# mother3.net
KiCad netlist of a schematic drawn in EAGLE
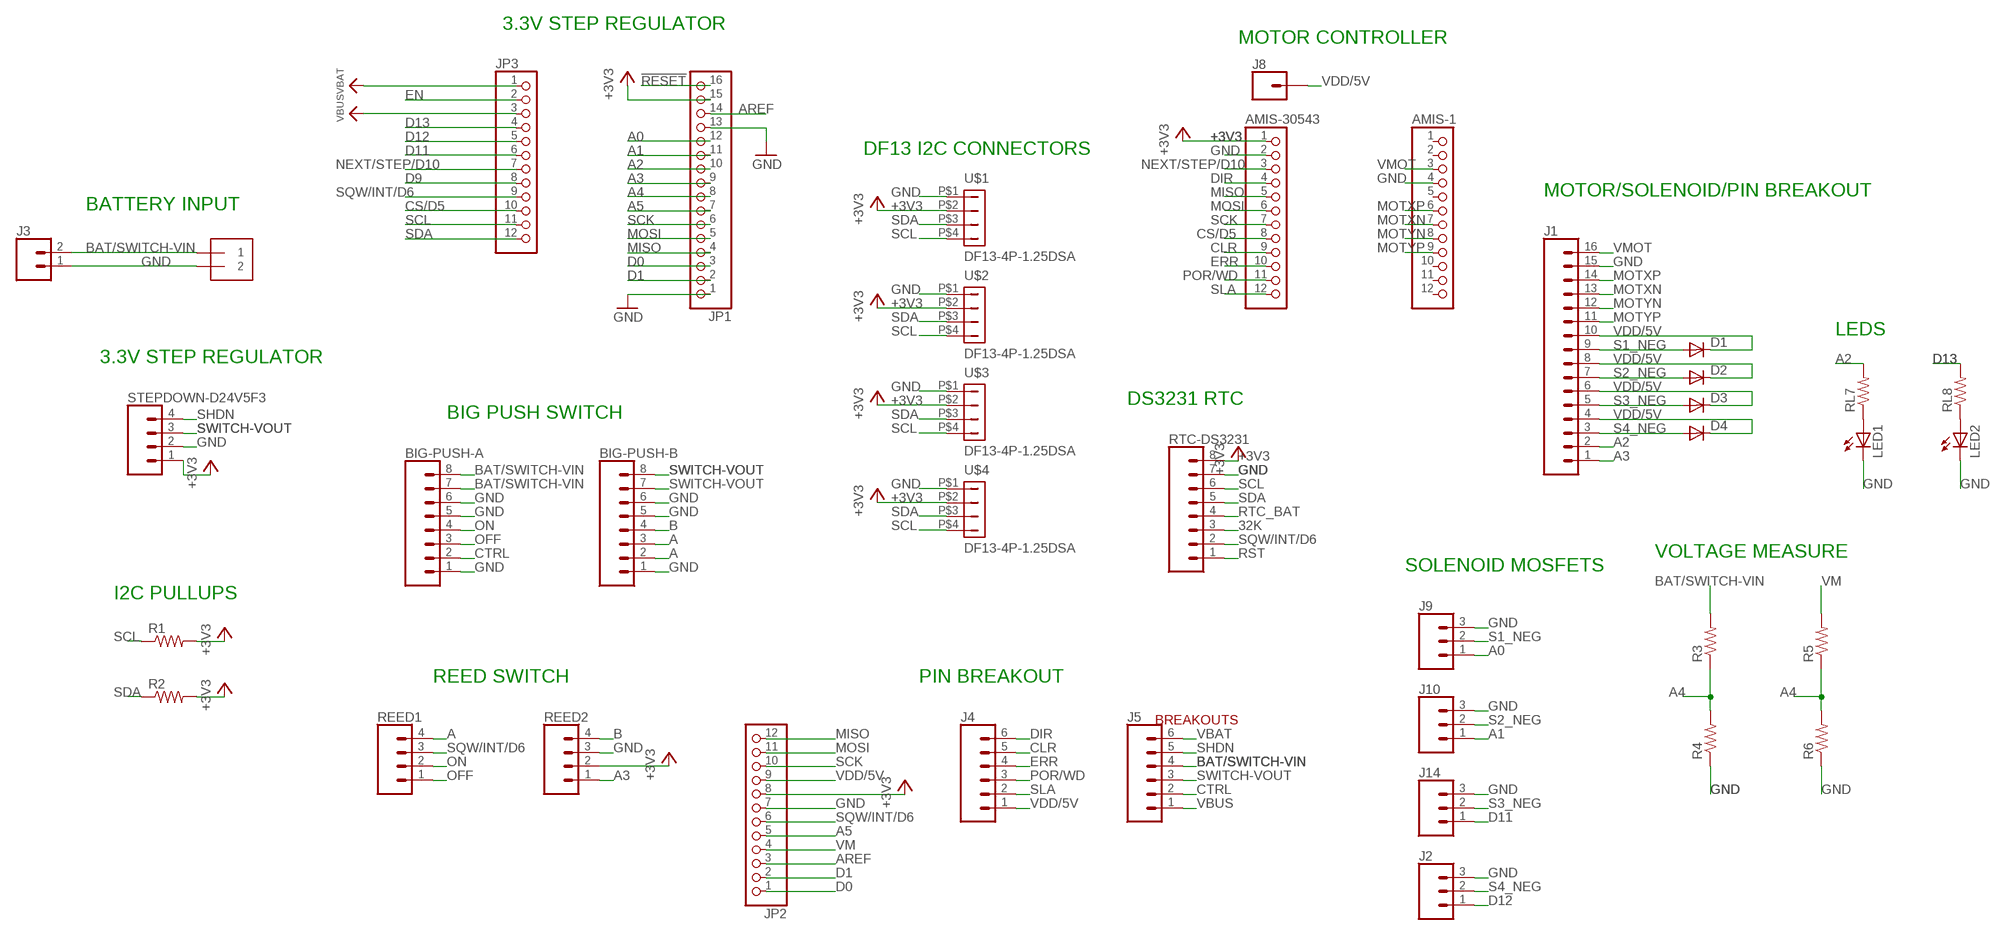
[diagram p0: schematic, sheet 1]

(export (version "E")
  (design (tool "Eeschema 10.0.6"))
  (components
    (comp (ref "AMIS-1")
      (value "PINHD-1X12-CB")
      (footprint "eagle-import:1X12-CB")
      (libsource (lib "eagle-import") (part "PINHD-1X12-CB"))
    )
    (comp (ref "AMIS-30543")
      (value "PINHD-1X12-CB")
      (footprint "eagle-import:1X12-CB")
      (libsource (lib "eagle-import") (part "PINHD-1X12-CB"))
    )
    (comp (ref "BAT")
      (value "1X2-3.5MM")
      (footprint "eagle-import:1X2-3.5MM")
      (libsource (lib "eagle-import") (part "1X2-3.5MM"))
    )
    (comp (ref "BIG-PUSH-A")
      (value "CONN_08\"")
      (footprint "eagle-import:1X08")
      (libsource (lib "eagle-import") (part "CONN_08{dblquote}"))
    )
    (comp (ref "BIG-PUSH-B")
      (value "CONN_08\"")
      (footprint "eagle-import:1X08")
      (libsource (lib "eagle-import") (part "CONN_08{dblquote}"))
    )
    (comp (ref "D1")
      (value "1N4148DO35-7")
      (footprint "eagle-import:DO35-7")
      (libsource (lib "eagle-import") (part "1N4148DO35-7"))
    )
    (comp (ref "D2")
      (value "1N4148DO35-7")
      (footprint "eagle-import:DO35-7")
      (libsource (lib "eagle-import") (part "1N4148DO35-7"))
    )
    (comp (ref "D3")
      (value "1N4148DO35-7")
      (footprint "eagle-import:DO35-7")
      (libsource (lib "eagle-import") (part "1N4148DO35-7"))
    )
    (comp (ref "D4")
      (value "1N4148DO35-7")
      (footprint "eagle-import:DO35-7")
      (libsource (lib "eagle-import") (part "1N4148DO35-7"))
    )
    (comp (ref "J1")
      (value "CONN_16")
      (footprint "eagle-import:1X16")
      (libsource (lib "eagle-import") (part "CONN_16"))
    )
    (comp (ref "J2")
      (value "CONN_03")
      (footprint "eagle-import:1X03")
      (libsource (lib "eagle-import") (part "CONN_03"))
    )
    (comp (ref "J3")
      (value "CONN_02")
      (footprint "eagle-import:1X02")
      (libsource (lib "eagle-import") (part "CONN_02"))
    )
    (comp (ref "J4")
      (value "CONN_06SILK_FEMALE_PTH")
      (footprint "eagle-import:1X06")
      (libsource (lib "eagle-import") (part "CONN_06SILK_FEMALE_PTH"))
    )
    (comp (ref "J5")
      (value "CONN_06SILK_FEMALE_PTH")
      (footprint "eagle-import:1X06")
      (libsource (lib "eagle-import") (part "CONN_06SILK_FEMALE_PTH"))
    )
    (comp (ref "J8")
      (value "CONN_01")
      (footprint "eagle-import:1X01")
      (libsource (lib "eagle-import") (part "CONN_01"))
    )
    (comp (ref "J9")
      (value "CONN_03")
      (footprint "eagle-import:1X03")
      (libsource (lib "eagle-import") (part "CONN_03"))
    )
    (comp (ref "J10")
      (value "CONN_03")
      (footprint "eagle-import:1X03")
      (libsource (lib "eagle-import") (part "CONN_03"))
    )
    (comp (ref "J14")
      (value "CONN_03")
      (footprint "eagle-import:1X03")
      (libsource (lib "eagle-import") (part "CONN_03"))
    )
    (comp (ref "JP1")
      (value "HEADER-1X16ROUND")
      (footprint "eagle-import:1X16_ROUND")
      (libsource (lib "eagle-import") (part "HEADER-1X16ROUND"))
    )
    (comp (ref "JP2")
      (value "HEADER-1X12")
      (footprint "eagle-import:1X12_ROUND")
      (libsource (lib "eagle-import") (part "HEADER-1X12"))
    )
    (comp (ref "JP3")
      (value "HEADER-1X12")
      (footprint "eagle-import:1X12_ROUND")
      (libsource (lib "eagle-import") (part "HEADER-1X12"))
    )
    (comp (ref "LED1")
      (value "LED5MM")
      (footprint "eagle-import:LED5MM")
      (libsource (lib "eagle-import") (part "LED5MM"))
    )
    (comp (ref "LED2")
      (value "LED5MM")
      (footprint "eagle-import:LED5MM")
      (libsource (lib "eagle-import") (part "LED5MM"))
    )
    (comp (ref "R1")
      (value "R-US_0207/10")
      (footprint "eagle-import:0207_10")
      (libsource (lib "eagle-import") (part "R-US_0207/10"))
    )
    (comp (ref "R2")
      (value "R-US_0207/10")
      (footprint "eagle-import:0207_10")
      (libsource (lib "eagle-import") (part "R-US_0207/10"))
    )
    (comp (ref "R3")
      (value "R-US_0207/10")
      (footprint "eagle-import:0207_10")
      (libsource (lib "eagle-import") (part "R-US_0207/10"))
    )
    (comp (ref "R4")
      (value "R-US_0207/10")
      (footprint "eagle-import:0207_10")
      (libsource (lib "eagle-import") (part "R-US_0207/10"))
    )
    (comp (ref "R5")
      (value "R-US_0207/10")
      (footprint "eagle-import:0207_10")
      (libsource (lib "eagle-import") (part "R-US_0207/10"))
    )
    (comp (ref "R6")
      (value "R-US_0207/10")
      (footprint "eagle-import:0207_10")
      (libsource (lib "eagle-import") (part "R-US_0207/10"))
    )
    (comp (ref "REED1")
      (value "CONN_04")
      (footprint "eagle-import:1X04")
      (libsource (lib "eagle-import") (part "CONN_04"))
    )
    (comp (ref "REED2")
      (value "CONN_04")
      (footprint "eagle-import:1X04")
      (libsource (lib "eagle-import") (part "CONN_04"))
    )
    (comp (ref "RL7")
      (value "R-US_0207/10")
      (footprint "eagle-import:0207_10")
      (libsource (lib "eagle-import") (part "R-US_0207/10"))
    )
    (comp (ref "RL8")
      (value "R-US_0207/10")
      (footprint "eagle-import:0207_10")
      (libsource (lib "eagle-import") (part "R-US_0207/10"))
    )
    (comp (ref "RTC-DS3231")
      (value "CONN_08\"")
      (footprint "eagle-import:1X08")
      (libsource (lib "eagle-import") (part "CONN_08{dblquote}"))
    )
    (comp (ref "STEPDOWN-D24V5F3")
      (value "CONN_04")
      (footprint "eagle-import:1X04")
      (libsource (lib "eagle-import") (part "CONN_04"))
    )
    (comp (ref "U$1")
      (value "DF13-4P-1.25DSA")
      (footprint "eagle-import:DF13-4P-1.25DSA")
      (libsource (lib "eagle-import") (part "DF13-4P-1.25DSA"))
    )
    (comp (ref "U$2")
      (value "DF13-4P-1.25DSA")
      (footprint "eagle-import:DF13-4P-1.25DSA")
      (libsource (lib "eagle-import") (part "DF13-4P-1.25DSA"))
    )
    (comp (ref "U$3")
      (value "DF13-4P-1.25DSA")
      (footprint "eagle-import:DF13-4P-1.25DSA")
      (libsource (lib "eagle-import") (part "DF13-4P-1.25DSA"))
    )
    (comp (ref "U$4")
      (value "DF13-4P-1.25DSA")
      (footprint "eagle-import:DF13-4P-1.25DSA")
      (libsource (lib "eagle-import") (part "DF13-4P-1.25DSA"))
    )
  )
  (nets
    (net (code "1") (name "+3V3") (class "Default")
      (node (ref "AMIS-30543") (pin "1") (pinfunction "1_1") (pintype "passive"))
      (node (ref "JP1") (pin "15") (pinfunction "15_15") (pintype "passive"))
      (node (ref "JP2") (pin "8") (pinfunction "8_8") (pintype "passive"))
      (node (ref "R1") (pin "2") (pinfunction "2_2") (pintype "passive"))
      (node (ref "R2") (pin "2") (pinfunction "2_2") (pintype "passive"))
      (node (ref "REED2") (pin "2") (pinfunction "2_2") (pintype "passive"))
      (node (ref "RTC-DS3231") (pin "8") (pinfunction "8_8") (pintype "passive"))
      (node (ref "STEPDOWN-D24V5F3") (pin "1") (pinfunction "1_1") (pintype "passive"))
      (node (ref "U$1") (pin "P$2") (pinfunction "2_P$2") (pintype "passive"))
      (node (ref "U$2") (pin "P$2") (pinfunction "2_P$2") (pintype "passive"))
      (node (ref "U$3") (pin "P$2") (pinfunction "2_P$2") (pintype "passive"))
      (node (ref "U$4") (pin "P$2") (pinfunction "2_P$2") (pintype "passive"))
    )
    (net (code "2") (name "/32K") (class "Default")
      (node (ref "RTC-DS3231") (pin "3") (pinfunction "3_3") (pintype "passive"))
    )
    (net (code "3") (name "/A") (class "Default")
      (node (ref "BIG-PUSH-B") (pin "2") (pinfunction "2_2") (pintype "passive"))
      (node (ref "BIG-PUSH-B") (pin "3") (pinfunction "3_3") (pintype "passive"))
      (node (ref "REED1") (pin "4") (pinfunction "4_4") (pintype "passive"))
    )
    (net (code "4") (name "/A0") (class "Default")
      (node (ref "J9") (pin "1") (pinfunction "1_1") (pintype "passive"))
      (node (ref "JP1") (pin "12") (pinfunction "12_12") (pintype "passive"))
    )
    (net (code "5") (name "/A1") (class "Default")
      (node (ref "J10") (pin "1") (pinfunction "1_1") (pintype "passive"))
      (node (ref "JP1") (pin "11") (pinfunction "11_11") (pintype "passive"))
    )
    (net (code "6") (name "/A2") (class "Default")
      (node (ref "J1") (pin "2") (pinfunction "2_2") (pintype "passive"))
      (node (ref "JP1") (pin "10") (pinfunction "10_10") (pintype "passive"))
      (node (ref "RL7") (pin "2") (pinfunction "2_2") (pintype "passive"))
    )
    (net (code "7") (name "/A3") (class "Default")
      (node (ref "J1") (pin "1") (pinfunction "1_1") (pintype "passive"))
      (node (ref "JP1") (pin "9") (pinfunction "9_9") (pintype "passive"))
      (node (ref "REED2") (pin "1") (pinfunction "1_1") (pintype "passive"))
    )
    (net (code "8") (name "/A4") (class "Default")
      (node (ref "JP1") (pin "8") (pinfunction "8_8") (pintype "passive"))
      (node (ref "R3") (pin "1") (pinfunction "1_1") (pintype "passive"))
      (node (ref "R4") (pin "2") (pinfunction "2_2") (pintype "passive"))
      (node (ref "R5") (pin "1") (pinfunction "1_1") (pintype "passive"))
      (node (ref "R6") (pin "2") (pinfunction "2_2") (pintype "passive"))
    )
    (net (code "9") (name "/A5") (class "Default")
      (node (ref "JP1") (pin "7") (pinfunction "7_7") (pintype "passive"))
      (node (ref "JP2") (pin "5") (pinfunction "5_5") (pintype "passive"))
    )
    (net (code "10") (name "/AREF") (class "Default")
      (node (ref "JP1") (pin "14") (pinfunction "14_14") (pintype "passive"))
      (node (ref "JP2") (pin "3") (pinfunction "3_3") (pintype "passive"))
    )
    (net (code "11") (name "/B") (class "Default")
      (node (ref "BIG-PUSH-B") (pin "4") (pinfunction "4_4") (pintype "passive"))
      (node (ref "REED2") (pin "4") (pinfunction "4_4") (pintype "passive"))
    )
    (net (code "12") (name "/BAT{slash}SWITCH-VIN") (class "Default")
      (node (ref "BAT") (pin "1") (pinfunction "1_1") (pintype "passive"))
      (node (ref "BIG-PUSH-A") (pin "7") (pinfunction "7_7") (pintype "passive"))
      (node (ref "BIG-PUSH-A") (pin "8") (pinfunction "8_8") (pintype "passive"))
      (node (ref "J3") (pin "2") (pinfunction "2_2") (pintype "passive"))
      (node (ref "J5") (pin "4") (pinfunction "4_4") (pintype "passive"))
      (node (ref "R3") (pin "2") (pinfunction "2_2") (pintype "passive"))
    )
    (net (code "13") (name "/CLR") (class "Default")
      (node (ref "AMIS-30543") (pin "9") (pinfunction "9_9") (pintype "passive"))
      (node (ref "J4") (pin "5") (pinfunction "5_5") (pintype "passive"))
    )
    (net (code "14") (name "/CS{slash}D5") (class "Default")
      (node (ref "AMIS-30543") (pin "8") (pinfunction "8_8") (pintype "passive"))
      (node (ref "JP3") (pin "10") (pinfunction "10_10") (pintype "passive"))
    )
    (net (code "15") (name "/CTRL") (class "Default")
      (node (ref "BIG-PUSH-A") (pin "2") (pinfunction "2_2") (pintype "passive"))
      (node (ref "J5") (pin "2") (pinfunction "2_2") (pintype "passive"))
    )
    (net (code "16") (name "/D0") (class "Default")
      (node (ref "JP1") (pin "3") (pinfunction "3_3") (pintype "passive"))
      (node (ref "JP2") (pin "1") (pinfunction "1_1") (pintype "passive"))
    )
    (net (code "17") (name "/D1") (class "Default")
      (node (ref "JP1") (pin "2") (pinfunction "2_2") (pintype "passive"))
      (node (ref "JP2") (pin "2") (pinfunction "2_2") (pintype "passive"))
    )
    (net (code "18") (name "/D9") (class "Default")
      (node (ref "JP3") (pin "8") (pinfunction "8_8") (pintype "passive"))
    )
    (net (code "19") (name "/D11") (class "Default")
      (node (ref "J14") (pin "1") (pinfunction "1_1") (pintype "passive"))
      (node (ref "JP3") (pin "6") (pinfunction "6_6") (pintype "passive"))
    )
    (net (code "20") (name "/D12") (class "Default")
      (node (ref "J2") (pin "1") (pinfunction "1_1") (pintype "passive"))
      (node (ref "JP3") (pin "5") (pinfunction "5_5") (pintype "passive"))
    )
    (net (code "21") (name "/D13") (class "Default")
      (node (ref "JP3") (pin "4") (pinfunction "4_4") (pintype "passive"))
      (node (ref "RL8") (pin "2") (pinfunction "2_2") (pintype "passive"))
    )
    (net (code "22") (name "/DIR") (class "Default")
      (node (ref "AMIS-30543") (pin "4") (pinfunction "4_4") (pintype "passive"))
      (node (ref "J4") (pin "6") (pinfunction "6_6") (pintype "passive"))
    )
    (net (code "23") (name "/EN") (class "Default")
      (node (ref "JP3") (pin "2") (pinfunction "2_2") (pintype "passive"))
    )
    (net (code "24") (name "/ERR") (class "Default")
      (node (ref "AMIS-30543") (pin "10") (pinfunction "10_10") (pintype "passive"))
      (node (ref "J4") (pin "4") (pinfunction "4_4") (pintype "passive"))
    )
    (net (code "25") (name "/MISO") (class "Default")
      (node (ref "AMIS-30543") (pin "5") (pinfunction "5_5") (pintype "passive"))
      (node (ref "JP1") (pin "4") (pinfunction "4_4") (pintype "passive"))
      (node (ref "JP2") (pin "12") (pinfunction "12_12") (pintype "passive"))
    )
    (net (code "26") (name "/MOSI") (class "Default")
      (node (ref "AMIS-30543") (pin "6") (pinfunction "6_6") (pintype "passive"))
      (node (ref "JP1") (pin "5") (pinfunction "5_5") (pintype "passive"))
      (node (ref "JP2") (pin "11") (pinfunction "11_11") (pintype "passive"))
    )
    (net (code "27") (name "/MOTXN") (class "Default")
      (node (ref "AMIS-1") (pin "7") (pinfunction "7_7") (pintype "passive"))
      (node (ref "J1") (pin "13") (pinfunction "13_13") (pintype "passive"))
    )
    (net (code "28") (name "/MOTXP") (class "Default")
      (node (ref "AMIS-1") (pin "6") (pinfunction "6_6") (pintype "passive"))
      (node (ref "J1") (pin "14") (pinfunction "14_14") (pintype "passive"))
    )
    (net (code "29") (name "/MOTYN") (class "Default")
      (node (ref "AMIS-1") (pin "8") (pinfunction "8_8") (pintype "passive"))
      (node (ref "J1") (pin "12") (pinfunction "12_12") (pintype "passive"))
    )
    (net (code "30") (name "/MOTYP") (class "Default")
      (node (ref "AMIS-1") (pin "9") (pinfunction "9_9") (pintype "passive"))
      (node (ref "J1") (pin "11") (pinfunction "11_11") (pintype "passive"))
    )
    (net (code "31") (name "/NEXT{slash}STEP{slash}D10") (class "Default")
      (node (ref "AMIS-30543") (pin "3") (pinfunction "3_3") (pintype "passive"))
      (node (ref "JP3") (pin "7") (pinfunction "7_7") (pintype "passive"))
    )
    (net (code "32") (name "/OFF") (class "Default")
      (node (ref "BIG-PUSH-A") (pin "3") (pinfunction "3_3") (pintype "passive"))
      (node (ref "REED1") (pin "1") (pinfunction "1_1") (pintype "passive"))
    )
    (net (code "33") (name "/ON") (class "Default")
      (node (ref "BIG-PUSH-A") (pin "4") (pinfunction "4_4") (pintype "passive"))
      (node (ref "REED1") (pin "2") (pinfunction "2_2") (pintype "passive"))
    )
    (net (code "34") (name "/POR{slash}WD") (class "Default")
      (node (ref "AMIS-30543") (pin "11") (pinfunction "11_11") (pintype "passive"))
      (node (ref "J4") (pin "3") (pinfunction "3_3") (pintype "passive"))
    )
    (net (code "35") (name "/RST") (class "Default")
      (node (ref "RTC-DS3231") (pin "1") (pinfunction "1_1") (pintype "passive"))
    )
    (net (code "36") (name "/RTC_BAT") (class "Default")
      (node (ref "RTC-DS3231") (pin "4") (pinfunction "4_4") (pintype "passive"))
    )
    (net (code "37") (name "/S1_NEG") (class "Default")
      (node (ref "D1") (pin "A") (pinfunction "A_A") (pintype "passive"))
      (node (ref "J1") (pin "9") (pinfunction "9_9") (pintype "passive"))
      (node (ref "J9") (pin "2") (pinfunction "2_2") (pintype "passive"))
    )
    (net (code "38") (name "/S2_NEG") (class "Default")
      (node (ref "D2") (pin "A") (pinfunction "A_A") (pintype "passive"))
      (node (ref "J1") (pin "7") (pinfunction "7_7") (pintype "passive"))
      (node (ref "J10") (pin "2") (pinfunction "2_2") (pintype "passive"))
    )
    (net (code "39") (name "/S3_NEG") (class "Default")
      (node (ref "D3") (pin "A") (pinfunction "A_A") (pintype "passive"))
      (node (ref "J1") (pin "5") (pinfunction "5_5") (pintype "passive"))
      (node (ref "J14") (pin "2") (pinfunction "2_2") (pintype "passive"))
    )
    (net (code "40") (name "/S4_NEG") (class "Default")
      (node (ref "D4") (pin "A") (pinfunction "A_A") (pintype "passive"))
      (node (ref "J1") (pin "3") (pinfunction "3_3") (pintype "passive"))
      (node (ref "J2") (pin "2") (pinfunction "2_2") (pintype "passive"))
    )
    (net (code "41") (name "/SCK") (class "Default")
      (node (ref "AMIS-30543") (pin "7") (pinfunction "7_7") (pintype "passive"))
      (node (ref "JP1") (pin "6") (pinfunction "6_6") (pintype "passive"))
      (node (ref "JP2") (pin "10") (pinfunction "10_10") (pintype "passive"))
    )
    (net (code "42") (name "/SCL") (class "Default")
      (node (ref "JP3") (pin "11") (pinfunction "11_11") (pintype "passive"))
      (node (ref "R1") (pin "1") (pinfunction "1_1") (pintype "passive"))
      (node (ref "RTC-DS3231") (pin "6") (pinfunction "6_6") (pintype "passive"))
      (node (ref "U$1") (pin "P$4") (pinfunction "4_P$4") (pintype "passive"))
      (node (ref "U$2") (pin "P$4") (pinfunction "4_P$4") (pintype "passive"))
      (node (ref "U$3") (pin "P$4") (pinfunction "4_P$4") (pintype "passive"))
      (node (ref "U$4") (pin "P$4") (pinfunction "4_P$4") (pintype "passive"))
    )
    (net (code "43") (name "/SDA") (class "Default")
      (node (ref "JP3") (pin "12") (pinfunction "12_12") (pintype "passive"))
      (node (ref "R2") (pin "1") (pinfunction "1_1") (pintype "passive"))
      (node (ref "RTC-DS3231") (pin "5") (pinfunction "5_5") (pintype "passive"))
      (node (ref "U$1") (pin "P$3") (pinfunction "3_P$3") (pintype "passive"))
      (node (ref "U$2") (pin "P$3") (pinfunction "3_P$3") (pintype "passive"))
      (node (ref "U$3") (pin "P$3") (pinfunction "3_P$3") (pintype "passive"))
      (node (ref "U$4") (pin "P$3") (pinfunction "3_P$3") (pintype "passive"))
    )
    (net (code "44") (name "/SHDN") (class "Default")
      (node (ref "J5") (pin "5") (pinfunction "5_5") (pintype "passive"))
      (node (ref "STEPDOWN-D24V5F3") (pin "4") (pinfunction "4_4") (pintype "passive"))
    )
    (net (code "45") (name "/SLA") (class "Default")
      (node (ref "AMIS-30543") (pin "12") (pinfunction "12_12") (pintype "passive"))
      (node (ref "J4") (pin "2") (pinfunction "2_2") (pintype "passive"))
    )
    (net (code "46") (name "/SQW{slash}INT{slash}D6") (class "Default")
      (node (ref "JP2") (pin "6") (pinfunction "6_6") (pintype "passive"))
      (node (ref "JP3") (pin "9") (pinfunction "9_9") (pintype "passive"))
      (node (ref "REED1") (pin "3") (pinfunction "3_3") (pintype "passive"))
      (node (ref "RTC-DS3231") (pin "2") (pinfunction "2_2") (pintype "passive"))
    )
    (net (code "47") (name "/SWITCH-VOUT") (class "Default")
      (node (ref "BIG-PUSH-B") (pin "7") (pinfunction "7_7") (pintype "passive"))
      (node (ref "BIG-PUSH-B") (pin "8") (pinfunction "8_8") (pintype "passive"))
      (node (ref "J5") (pin "3") (pinfunction "3_3") (pintype "passive"))
      (node (ref "STEPDOWN-D24V5F3") (pin "3") (pinfunction "3_3") (pintype "passive"))
    )
    (net (code "48") (name "/VDD{slash}5V") (class "Default")
      (node (ref "D1") (pin "C") (pinfunction "C_C") (pintype "passive"))
      (node (ref "D2") (pin "C") (pinfunction "C_C") (pintype "passive"))
      (node (ref "D3") (pin "C") (pinfunction "C_C") (pintype "passive"))
      (node (ref "D4") (pin "C") (pinfunction "C_C") (pintype "passive"))
      (node (ref "J1") (pin "10") (pinfunction "10_10") (pintype "passive"))
      (node (ref "J1") (pin "4") (pinfunction "4_4") (pintype "passive"))
      (node (ref "J1") (pin "6") (pinfunction "6_6") (pintype "passive"))
      (node (ref "J1") (pin "8") (pinfunction "8_8") (pintype "passive"))
      (node (ref "J4") (pin "1") (pinfunction "1_1") (pintype "passive"))
      (node (ref "J8") (pin "1") (pinfunction "1_1") (pintype "passive"))
      (node (ref "JP2") (pin "9") (pinfunction "9_9") (pintype "passive"))
    )
    (net (code "49") (name "/VM") (class "Default")
      (node (ref "JP2") (pin "4") (pinfunction "4_4") (pintype "passive"))
      (node (ref "R5") (pin "2") (pinfunction "2_2") (pintype "passive"))
    )
    (net (code "50") (name "/VMOT") (class "Default")
      (node (ref "AMIS-1") (pin "3") (pinfunction "3_3") (pintype "passive"))
      (node (ref "J1") (pin "16") (pinfunction "16_16") (pintype "passive"))
    )
    (net (code "51") (name "/~{RESET}") (class "Default")
      (node (ref "JP1") (pin "16") (pinfunction "16_16") (pintype "passive"))
    )
    (net (code "52") (name "GND") (class "Default")
      (node (ref "AMIS-1") (pin "4") (pinfunction "4_4") (pintype "passive"))
      (node (ref "AMIS-30543") (pin "2") (pinfunction "2_2") (pintype "passive"))
      (node (ref "BAT") (pin "2") (pinfunction "2_2") (pintype "passive"))
      (node (ref "BIG-PUSH-A") (pin "1") (pinfunction "1_1") (pintype "passive"))
      (node (ref "BIG-PUSH-A") (pin "5") (pinfunction "5_5") (pintype "passive"))
      (node (ref "BIG-PUSH-A") (pin "6") (pinfunction "6_6") (pintype "passive"))
      (node (ref "BIG-PUSH-B") (pin "1") (pinfunction "1_1") (pintype "passive"))
      (node (ref "BIG-PUSH-B") (pin "5") (pinfunction "5_5") (pintype "passive"))
      (node (ref "BIG-PUSH-B") (pin "6") (pinfunction "6_6") (pintype "passive"))
      (node (ref "J1") (pin "15") (pinfunction "15_15") (pintype "passive"))
      (node (ref "J10") (pin "3") (pinfunction "3_3") (pintype "passive"))
      (node (ref "J14") (pin "3") (pinfunction "3_3") (pintype "passive"))
      (node (ref "J2") (pin "3") (pinfunction "3_3") (pintype "passive"))
      (node (ref "J3") (pin "1") (pinfunction "1_1") (pintype "passive"))
      (node (ref "J9") (pin "3") (pinfunction "3_3") (pintype "passive"))
      (node (ref "JP1") (pin "1") (pinfunction "1_1") (pintype "passive"))
      (node (ref "JP1") (pin "13") (pinfunction "13_13") (pintype "passive"))
      (node (ref "JP2") (pin "7") (pinfunction "7_7") (pintype "passive"))
      (node (ref "LED1") (pin "K") (pinfunction "C_K") (pintype "passive"))
      (node (ref "LED2") (pin "K") (pinfunction "C_K") (pintype "passive"))
      (node (ref "R4") (pin "1") (pinfunction "1_1") (pintype "passive"))
      (node (ref "R6") (pin "1") (pinfunction "1_1") (pintype "passive"))
      (node (ref "REED2") (pin "3") (pinfunction "3_3") (pintype "passive"))
      (node (ref "RTC-DS3231") (pin "7") (pinfunction "7_7") (pintype "passive"))
      (node (ref "STEPDOWN-D24V5F3") (pin "2") (pinfunction "2_2") (pintype "passive"))
      (node (ref "U$1") (pin "P$1") (pinfunction "1_P$1") (pintype "passive"))
      (node (ref "U$2") (pin "P$1") (pinfunction "1_P$1") (pintype "passive"))
      (node (ref "U$3") (pin "P$1") (pinfunction "1_P$1") (pintype "passive"))
      (node (ref "U$4") (pin "P$1") (pinfunction "1_P$1") (pintype "passive"))
    )
    (net (code "53") (name "Net-(LED1-PadA)") (class "Default")
      (node (ref "LED1") (pin "A") (pinfunction "A_A") (pintype "passive"))
      (node (ref "RL7") (pin "1") (pinfunction "1_1") (pintype "passive"))
    )
    (net (code "54") (name "Net-(LED2-PadA)") (class "Default")
      (node (ref "LED2") (pin "A") (pinfunction "A_A") (pintype "passive"))
      (node (ref "RL8") (pin "1") (pinfunction "1_1") (pintype "passive"))
    )
    (net (code "55") (name "VBAT") (class "Default")
      (node (ref "J5") (pin "6") (pinfunction "6_6") (pintype "passive"))
      (node (ref "JP3") (pin "1") (pinfunction "1_1") (pintype "passive"))
    )
    (net (code "56") (name "VBUS") (class "Default")
      (node (ref "J5") (pin "1") (pinfunction "1_1") (pintype "passive"))
      (node (ref "JP3") (pin "3") (pinfunction "3_3") (pintype "passive"))
    )
    (net (code "57") (name "unconnected-(AMIS-1-Pad1)") (class "Default")
      (node (ref "AMIS-1") (pin "1") (pinfunction "1_1") (pintype "passive"))
    )
    (net (code "58") (name "unconnected-(AMIS-1-Pad2)") (class "Default")
      (node (ref "AMIS-1") (pin "2") (pinfunction "2_2") (pintype "passive"))
    )
    (net (code "59") (name "unconnected-(AMIS-1-Pad5)") (class "Default")
      (node (ref "AMIS-1") (pin "5") (pinfunction "5_5") (pintype "passive"))
    )
    (net (code "60") (name "unconnected-(AMIS-1-Pad10)") (class "Default")
      (node (ref "AMIS-1") (pin "10") (pinfunction "10_10") (pintype "passive"))
    )
    (net (code "61") (name "unconnected-(AMIS-1-Pad11)") (class "Default")
      (node (ref "AMIS-1") (pin "11") (pinfunction "11_11") (pintype "passive"))
    )
    (net (code "62") (name "unconnected-(AMIS-1-Pad12)") (class "Default")
      (node (ref "AMIS-1") (pin "12") (pinfunction "12_12") (pintype "passive"))
    )
  )
)
